# ftdi.net
KiCad netlist of a schematic drawn in EAGLE
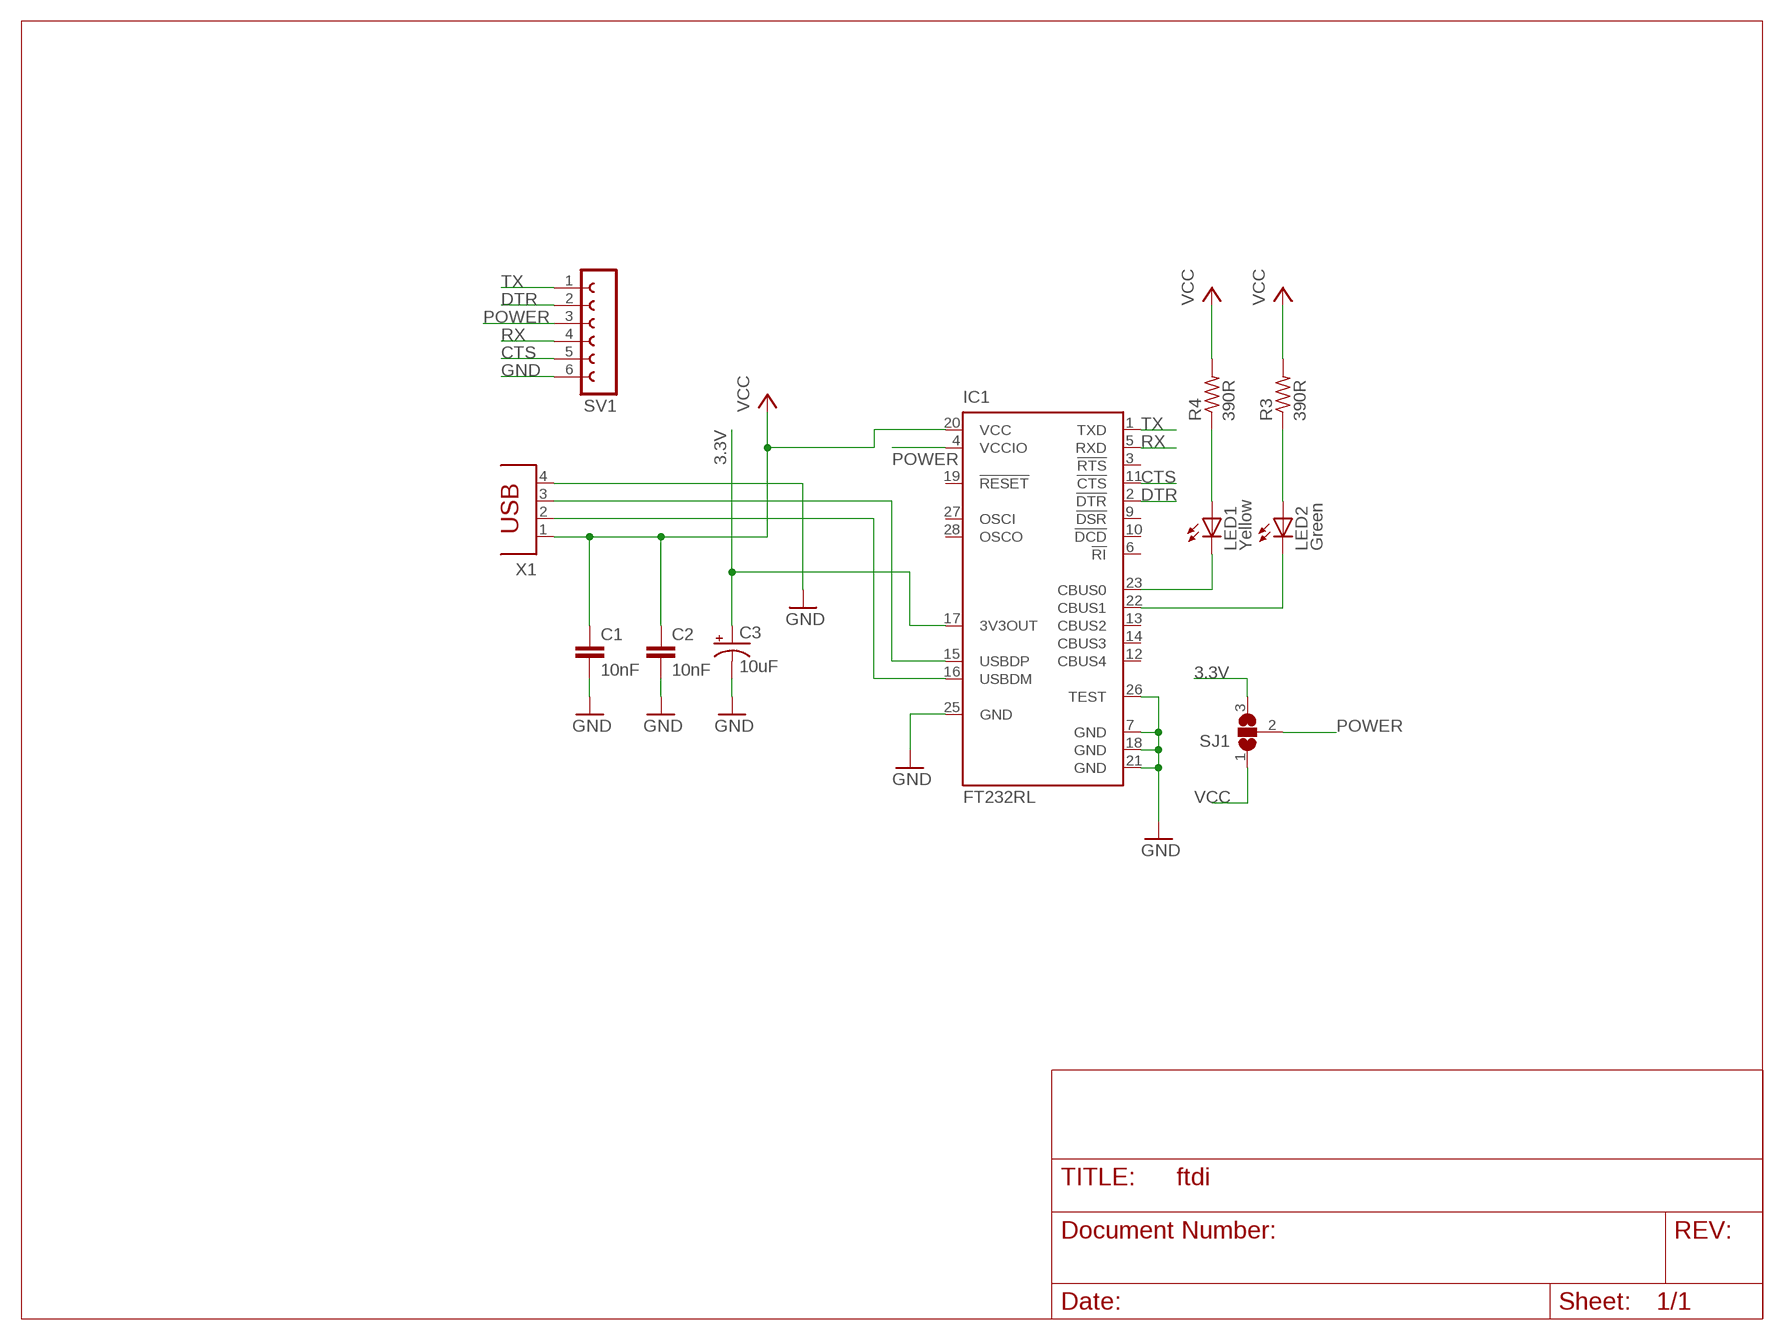
[diagram p0: schematic, sheet 1]

(export (version "E")
  (design (tool "Eeschema 10.0.6"))
  (components
    (comp (ref "C1")
      (value "10nF")
      (footprint "eagle-import:C0805")
      (libsource (lib "eagle-import") (part "C-EUC0805"))
    )
    (comp (ref "C2")
      (value "10nF")
      (footprint "eagle-import:C0805")
      (libsource (lib "eagle-import") (part "C-EUC0805"))
    )
    (comp (ref "C3")
      (value "10uF")
      (footprint "eagle-import:E2,5-6")
      (libsource (lib "eagle-import") (part "CPOL-USE2.5-6"))
    )
    (comp (ref "IC1")
      (value "FT232RL")
      (footprint "eagle-import:SSOP28")
      (libsource (lib "eagle-import") (part "FT232RL"))
    )
    (comp (ref "LED1")
      (value "Yellow")
      (footprint "eagle-import:LED5MM")
      (libsource (lib "eagle-import") (part "LED5MM"))
    )
    (comp (ref "LED2")
      (value "Green")
      (footprint "eagle-import:LED5MM")
      (libsource (lib "eagle-import") (part "LED5MM"))
    )
    (comp (ref "R3")
      (value "390R")
      (footprint "eagle-import:R0805")
      (libsource (lib "eagle-import") (part "R-US_R0805"))
    )
    (comp (ref "R4")
      (value "390R")
      (footprint "eagle-import:R0805")
      (libsource (lib "eagle-import") (part "R-US_R0805"))
    )
    (comp (ref "SJ1")
      (value "SJ2W")
      (footprint "eagle-import:SJ_2")
      (libsource (lib "eagle-import") (part "SJ2W"))
    )
    (comp (ref "SV1")
      (value "FE06-1")
      (footprint "eagle-import:FE06")
      (libsource (lib "eagle-import") (part "FE06-1"))
    )
    (comp (ref "X1")
      (value "PN87520")
      (footprint "eagle-import:PN87520")
      (libsource (lib "eagle-import") (part "PN87520"))
    )
  )
  (nets
    (net (code "1") (name "/3.3V") (class "Default")
      (node (ref "C3") (pin "+") (pinfunction "+_+") (pintype "passive"))
      (node (ref "IC1") (pin "17") (pinfunction "3V3OUT_17") (pintype "output"))
      (node (ref "SJ1") (pin "3") (pinfunction "3_3") (pintype "passive"))
    )
    (net (code "2") (name "/CTS") (class "Default")
      (node (ref "IC1") (pin "11") (pinfunction "~{CTS}_11") (pintype "input"))
      (node (ref "SV1") (pin "5") (pinfunction "5_5") (pintype "passive"))
    )
    (net (code "3") (name "/DTR") (class "Default")
      (node (ref "IC1") (pin "2") (pinfunction "~{DTR}_2") (pintype "output"))
      (node (ref "SV1") (pin "2") (pinfunction "2_2") (pintype "passive"))
    )
    (net (code "4") (name "/POWER") (class "Default")
      (node (ref "IC1") (pin "4") (pinfunction "VCCIO_4") (pintype "power_in"))
      (node (ref "SJ1") (pin "2") (pinfunction "2_2") (pintype "passive"))
      (node (ref "SV1") (pin "3") (pinfunction "3_3") (pintype "passive"))
    )
    (net (code "5") (name "/RX") (class "Default")
      (node (ref "IC1") (pin "5") (pinfunction "RXD_5") (pintype "input"))
      (node (ref "SV1") (pin "4") (pinfunction "4_4") (pintype "passive"))
    )
    (net (code "6") (name "/TX") (class "Default")
      (node (ref "IC1") (pin "1") (pinfunction "TXD_1") (pintype "output"))
      (node (ref "SV1") (pin "1") (pinfunction "1_1") (pintype "passive"))
    )
    (net (code "7") (name "GND") (class "Default")
      (node (ref "C1") (pin "2") (pinfunction "2_2") (pintype "passive"))
      (node (ref "C2") (pin "2") (pinfunction "2_2") (pintype "passive"))
      (node (ref "C3") (pin "-") (pinfunction "-_-") (pintype "passive"))
      (node (ref "IC1") (pin "18") (pinfunction "GND_18") (pintype "power_in"))
      (node (ref "IC1") (pin "21") (pinfunction "GND_21") (pintype "power_in"))
      (node (ref "IC1") (pin "25") (pinfunction "GND_25") (pintype "power_in"))
      (node (ref "IC1") (pin "26") (pinfunction "TEST_26") (pintype "input"))
      (node (ref "IC1") (pin "7") (pinfunction "GND_7") (pintype "power_in"))
      (node (ref "SV1") (pin "6") (pinfunction "6_6") (pintype "passive"))
      (node (ref "X1") (pin "4") (pinfunction "4_4") (pintype "passive"))
    )
    (net (code "8") (name "Net-(IC1-CBUS0)") (class "Default")
      (node (ref "IC1") (pin "23") (pinfunction "CBUS0_23") (pintype "bidirectional"))
      (node (ref "LED1") (pin "K") (pinfunction "C_K") (pintype "passive"))
    )
    (net (code "9") (name "Net-(IC1-CBUS1)") (class "Default")
      (node (ref "IC1") (pin "22") (pinfunction "CBUS1_22") (pintype "bidirectional"))
      (node (ref "LED2") (pin "K") (pinfunction "C_K") (pintype "passive"))
    )
    (net (code "10") (name "Net-(IC1-USBDM)") (class "Default")
      (node (ref "IC1") (pin "16") (pinfunction "USBDM_16") (pintype "bidirectional"))
      (node (ref "X1") (pin "2") (pinfunction "2_2") (pintype "passive"))
    )
    (net (code "11") (name "Net-(IC1-USBDP)") (class "Default")
      (node (ref "IC1") (pin "15") (pinfunction "USBDP_15") (pintype "bidirectional"))
      (node (ref "X1") (pin "3") (pinfunction "3_3") (pintype "passive"))
    )
    (net (code "12") (name "Net-(LED1-PadA)") (class "Default")
      (node (ref "LED1") (pin "A") (pinfunction "A_A") (pintype "passive"))
      (node (ref "R4") (pin "1") (pinfunction "1_1") (pintype "passive"))
    )
    (net (code "13") (name "Net-(LED2-PadA)") (class "Default")
      (node (ref "LED2") (pin "A") (pinfunction "A_A") (pintype "passive"))
      (node (ref "R3") (pin "1") (pinfunction "1_1") (pintype "passive"))
    )
    (net (code "14") (name "VCC") (class "Default")
      (node (ref "C1") (pin "1") (pinfunction "1_1") (pintype "passive"))
      (node (ref "C2") (pin "1") (pinfunction "1_1") (pintype "passive"))
      (node (ref "IC1") (pin "20") (pinfunction "VCC_20") (pintype "power_in"))
      (node (ref "R3") (pin "2") (pinfunction "2_2") (pintype "passive"))
      (node (ref "R4") (pin "2") (pinfunction "2_2") (pintype "passive"))
      (node (ref "SJ1") (pin "1") (pinfunction "1_1") (pintype "passive"))
      (node (ref "X1") (pin "1") (pinfunction "1_1") (pintype "passive"))
    )
    (net (code "15") (name "unconnected-(IC1-CBUS2-Pad13)") (class "Default")
      (node (ref "IC1") (pin "13") (pinfunction "CBUS2_13") (pintype "bidirectional"))
    )
    (net (code "16") (name "unconnected-(IC1-CBUS3-Pad14)") (class "Default")
      (node (ref "IC1") (pin "14") (pinfunction "CBUS3_14") (pintype "bidirectional"))
    )
    (net (code "17") (name "unconnected-(IC1-CBUS4-Pad12)") (class "Default")
      (node (ref "IC1") (pin "12") (pinfunction "CBUS4_12") (pintype "bidirectional"))
    )
    (net (code "18") (name "unconnected-(IC1-OSCI-Pad27)") (class "Default")
      (node (ref "IC1") (pin "27") (pinfunction "OSCI_27") (pintype "input"))
    )
    (net (code "19") (name "unconnected-(IC1-OSCO-Pad28)") (class "Default")
      (node (ref "IC1") (pin "28") (pinfunction "OSCO_28") (pintype "output"))
    )
    (net (code "20") (name "unconnected-(IC1-~{DCD}-Pad10)") (class "Default")
      (node (ref "IC1") (pin "10") (pinfunction "~{DCD}_10") (pintype "input"))
    )
    (net (code "21") (name "unconnected-(IC1-~{DSR}-Pad9)") (class "Default")
      (node (ref "IC1") (pin "9") (pinfunction "~{DSR}_9") (pintype "input"))
    )
    (net (code "22") (name "unconnected-(IC1-~{RESET}-Pad19)") (class "Default")
      (node (ref "IC1") (pin "19") (pinfunction "~{RESET}_19") (pintype "input"))
    )
    (net (code "23") (name "unconnected-(IC1-~{RI}-Pad6)") (class "Default")
      (node (ref "IC1") (pin "6") (pinfunction "~{RI}_6") (pintype "input"))
    )
    (net (code "24") (name "unconnected-(IC1-~{RTS}-Pad3)") (class "Default")
      (node (ref "IC1") (pin "3") (pinfunction "~{RTS}_3") (pintype "output"))
    )
  )
)
